# gpi-filter1.net
KiCad netlist of a schematic drawn in EAGLE
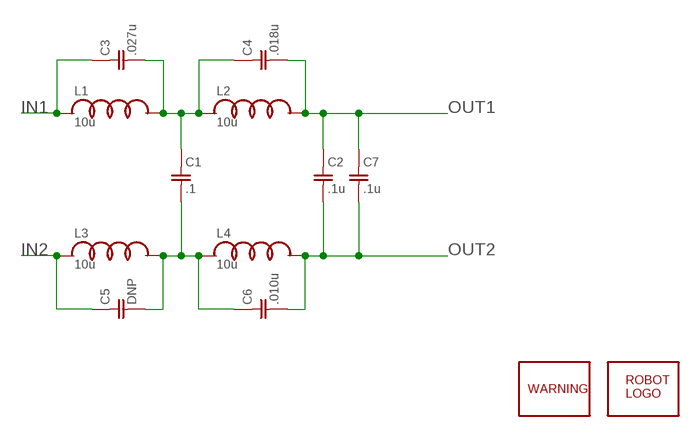
[diagram p0: schematic, sheet 1]

(export (version "E")
  (design (tool "Eeschema 10.0.6"))
  (components
    (comp (ref "C1")
      (value ".1")
      (footprint "eagle-import:SMD1210")
      (libsource (lib "eagle-import") (part "C1210"))
    )
    (comp (ref "C2")
      (value ".1u")
      (footprint "eagle-import:SMD1210")
      (libsource (lib "eagle-import") (part "C1210"))
    )
    (comp (ref "C3")
      (value ".027u")
      (footprint "eagle-import:SMD1210")
      (libsource (lib "eagle-import") (part "C1210"))
    )
    (comp (ref "C4")
      (value ".018u")
      (footprint "eagle-import:SMD1210")
      (libsource (lib "eagle-import") (part "C1210"))
    )
    (comp (ref "C5")
      (value "DNP")
      (footprint "eagle-import:SMD1210")
      (libsource (lib "eagle-import") (part "C1210"))
    )
    (comp (ref "C6")
      (value ".010u")
      (footprint "eagle-import:SMD1210")
      (libsource (lib "eagle-import") (part "C1210"))
    )
    (comp (ref "C7")
      (value ".1u")
      (footprint "eagle-import:SMD1210")
      (libsource (lib "eagle-import") (part "C1210"))
    )
    (comp (ref "L1")
      (value "10u")
      (footprint "eagle-import:XAL10")
      (libsource (lib "eagle-import") (part "LXAL10"))
    )
    (comp (ref "L2")
      (value "10u")
      (footprint "eagle-import:XAL10")
      (libsource (lib "eagle-import") (part "LXAL10"))
    )
    (comp (ref "L3")
      (value "10u")
      (footprint "eagle-import:XAL10")
      (libsource (lib "eagle-import") (part "LXAL10"))
    )
    (comp (ref "L4")
      (value "10u")
      (footprint "eagle-import:XAL10")
      (libsource (lib "eagle-import") (part "LXAL10"))
    )
    (comp (ref "U$1")
      (value "ROBOTMAN-LOGO")
      (footprint "eagle-import:ROBOTMAN-LOGO")
      (libsource (lib "eagle-import") (part "ROBOTMAN-LOGO"))
    )
    (comp (ref "U$2")
      (value "SYMBOL-WARNING")
      (footprint "eagle-import:SYMBOL-WARNING")
      (libsource (lib "eagle-import") (part "SYMBOL-WARNING"))
    )
  )
  (nets
    (net (code "1") (name "/IN1") (class "Default")
      (node (ref "C3") (pin "1") (pinfunction "P$1_1") (pintype "passive"))
      (node (ref "L1") (pin "P$1") (pinfunction "P$1_P$1") (pintype "passive"))
    )
    (net (code "2") (name "/IN2") (class "Default")
      (node (ref "C5") (pin "1") (pinfunction "P$1_1") (pintype "passive"))
      (node (ref "L3") (pin "P$1") (pinfunction "P$1_P$1") (pintype "passive"))
    )
    (net (code "3") (name "/OUT1") (class "Default")
      (node (ref "C2") (pin "1") (pinfunction "P$1_1") (pintype "passive"))
      (node (ref "C4") (pin "2") (pinfunction "P$2_2") (pintype "passive"))
      (node (ref "C7") (pin "1") (pinfunction "P$1_1") (pintype "passive"))
      (node (ref "L2") (pin "P$2") (pinfunction "P$2_P$2") (pintype "passive"))
    )
    (net (code "4") (name "/OUT2") (class "Default")
      (node (ref "C2") (pin "2") (pinfunction "P$2_2") (pintype "passive"))
      (node (ref "C6") (pin "2") (pinfunction "P$2_2") (pintype "passive"))
      (node (ref "C7") (pin "2") (pinfunction "P$2_2") (pintype "passive"))
      (node (ref "L4") (pin "P$2") (pinfunction "P$2_P$2") (pintype "passive"))
    )
    (net (code "5") (name "Net-(C1-P$1)") (class "Default")
      (node (ref "C1") (pin "1") (pinfunction "P$1_1") (pintype "passive"))
      (node (ref "C3") (pin "2") (pinfunction "P$2_2") (pintype "passive"))
      (node (ref "C4") (pin "1") (pinfunction "P$1_1") (pintype "passive"))
      (node (ref "L1") (pin "P$2") (pinfunction "P$2_P$2") (pintype "passive"))
      (node (ref "L2") (pin "P$1") (pinfunction "P$1_P$1") (pintype "passive"))
    )
    (net (code "6") (name "Net-(C1-P$2)") (class "Default")
      (node (ref "C1") (pin "2") (pinfunction "P$2_2") (pintype "passive"))
      (node (ref "C5") (pin "2") (pinfunction "P$2_2") (pintype "passive"))
      (node (ref "C6") (pin "1") (pinfunction "P$1_1") (pintype "passive"))
      (node (ref "L3") (pin "P$2") (pinfunction "P$2_P$2") (pintype "passive"))
      (node (ref "L4") (pin "P$1") (pinfunction "P$1_P$1") (pintype "passive"))
    )
  )
)
